# pmc2.net
KiCad netlist of a schematic drawn in EAGLE
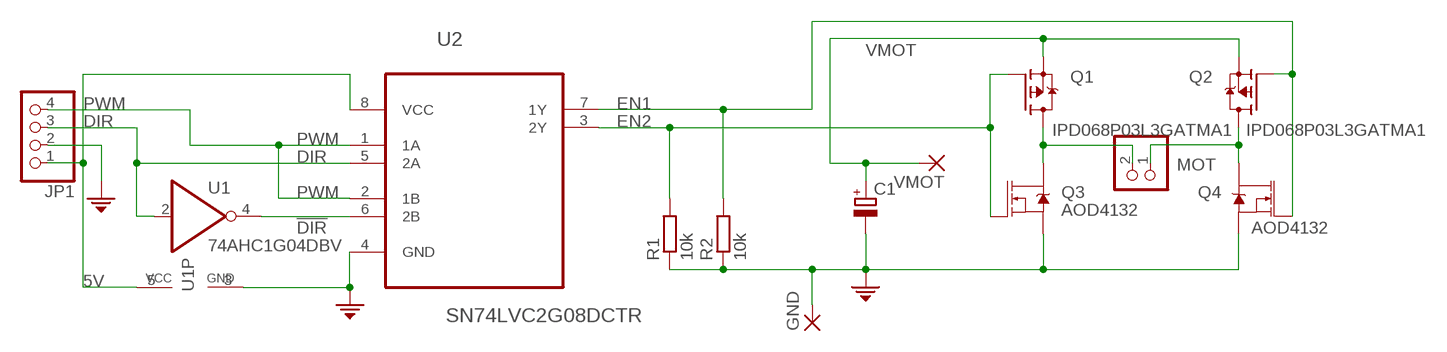
[diagram p0: schematic, sheet 1]

(export (version "E")
  (design (tool "Eeschema 10.0.6"))
  (components
    (comp (ref "C1")
      (value "CPOL-EUE5-13")
      (footprint "eagle-import:E5-13")
      (libsource (lib "eagle-import") (part "CPOL-EUE5-13"))
    )
    (comp (ref "GND")
      (value "SMD5")
      (footprint "eagle-import:SMD2,54-5,08")
      (libsource (lib "eagle-import") (part "SMD5"))
    )
    (comp (ref "JP1")
      (value "PINHD-1X4/90")
      (footprint "eagle-import:1X04_90")
      (libsource (lib "eagle-import") (part "PINHD-1X4/90"))
    )
    (comp (ref "MOT")
      (value "PINHD-1X2")
      (footprint "eagle-import:1X02")
      (libsource (lib "eagle-import") (part "PINHD-1X2"))
    )
    (comp (ref "Q1")
      (value "IPD068P03L3GATMA1")
      (footprint "eagle-import:TO252")
      (libsource (lib "eagle-import") (part "FDD4141TO252"))
    )
    (comp (ref "Q2")
      (value "IPD068P03L3GATMA1")
      (footprint "eagle-import:TO252")
      (libsource (lib "eagle-import") (part "FDD4141TO252"))
    )
    (comp (ref "Q3")
      (value "AOD4132")
      (footprint "eagle-import:DPAK")
      (libsource (lib "eagle-import") (part "MOSFET-NCH-FDD8780"))
    )
    (comp (ref "Q4")
      (value "AOD4132")
      (footprint "eagle-import:DPAK")
      (libsource (lib "eagle-import") (part "MOSFET-NCH-FDD8780"))
    )
    (comp (ref "R1")
      (value "10k")
      (footprint "eagle-import:R0603")
      (libsource (lib "eagle-import") (part "R-EU_R0603"))
    )
    (comp (ref "R2")
      (value "10k")
      (footprint "eagle-import:R0603")
      (libsource (lib "eagle-import") (part "R-EU_R0603"))
    )
    (comp (ref "U1")
      (value "74AHC1G04DBV")
      (footprint "eagle-import:SOT23-5")
      (libsource (lib "eagle-import") (part "741G04DBVAHC"))
    )
    (comp (ref "U2")
      (value "SN74LVC2G08DCTR")
      (footprint "eagle-import:SOP65P400X130-8N")
      (libsource (lib "eagle-import") (part "SN74LVC2G08DCTR"))
    )
    (comp (ref "VMOT")
      (value "SMD5")
      (footprint "eagle-import:SMD2,54-5,08")
      (libsource (lib "eagle-import") (part "SMD5"))
    )
  )
  (nets
    (net (code "1") (name "/5V") (class "Default")
      (node (ref "JP1") (pin "1") (pinfunction "1_1") (pintype "passive"))
      (node (ref "U1") (pin "5") (pinfunction "VCC_5") (pintype "power_in"))
      (node (ref "U2") (pin "8") (pinfunction "VCC_8") (pintype "power_in"))
    )
    (net (code "2") (name "/DIR") (class "Default")
      (node (ref "JP1") (pin "3") (pinfunction "3_3") (pintype "passive"))
      (node (ref "U1") (pin "2") (pinfunction "I_2") (pintype "input"))
      (node (ref "U2") (pin "5") (pinfunction "2A_5") (pintype "input"))
    )
    (net (code "3") (name "/EN1") (class "Default")
      (node (ref "Q2") (pin "1") (pinfunction "G_1") (pintype "passive"))
      (node (ref "Q4") (pin "1") (pinfunction "G_1") (pintype "bidirectional"))
      (node (ref "R2") (pin "2") (pinfunction "2_2") (pintype "passive"))
      (node (ref "U2") (pin "7") (pinfunction "1Y_7") (pintype "output"))
    )
    (net (code "4") (name "/EN2") (class "Default")
      (node (ref "Q1") (pin "1") (pinfunction "G_1") (pintype "passive"))
      (node (ref "Q3") (pin "1") (pinfunction "G_1") (pintype "bidirectional"))
      (node (ref "R1") (pin "2") (pinfunction "2_2") (pintype "passive"))
      (node (ref "U2") (pin "3") (pinfunction "2Y_3") (pintype "output"))
    )
    (net (code "5") (name "/PWM") (class "Default")
      (node (ref "JP1") (pin "4") (pinfunction "4_4") (pintype "passive"))
      (node (ref "U2") (pin "1") (pinfunction "1A_1") (pintype "input"))
      (node (ref "U2") (pin "2") (pinfunction "1B_2") (pintype "input"))
    )
    (net (code "6") (name "/VMOT") (class "Default")
      (node (ref "C1") (pin "+") (pinfunction "+_+") (pintype "passive"))
      (node (ref "Q1") (pin "2") (pinfunction "S_2") (pintype "passive"))
      (node (ref "Q2") (pin "2") (pinfunction "S_2") (pintype "passive"))
      (node (ref "VMOT") (pin "1") (pinfunction "P_1") (pintype "passive"))
    )
    (net (code "7") (name "/~{DIR}") (class "Default")
      (node (ref "U1") (pin "4") (pinfunction "O_4") (pintype "output"))
      (node (ref "U2") (pin "6") (pinfunction "2B_6") (pintype "input"))
    )
    (net (code "8") (name "GND") (class "Default")
      (node (ref "C1") (pin "-") (pinfunction "-_-") (pintype "passive"))
      (node (ref "GND") (pin "1") (pinfunction "P_1") (pintype "passive"))
      (node (ref "JP1") (pin "2") (pinfunction "2_2") (pintype "passive"))
      (node (ref "Q3") (pin "3") (pinfunction "S_3") (pintype "bidirectional"))
      (node (ref "Q4") (pin "3") (pinfunction "S_3") (pintype "bidirectional"))
      (node (ref "R1") (pin "1") (pinfunction "1_1") (pintype "passive"))
      (node (ref "R2") (pin "1") (pinfunction "1_1") (pintype "passive"))
      (node (ref "U1") (pin "3") (pinfunction "GND_3") (pintype "power_in"))
      (node (ref "U2") (pin "4") (pinfunction "GND_4") (pintype "passive"))
    )
    (net (code "9") (name "Net-(Q1-D)") (class "Default")
      (node (ref "MOT") (pin "2") (pinfunction "2_2") (pintype "passive"))
      (node (ref "Q1") (pin "3") (pinfunction "D_3") (pintype "passive"))
      (node (ref "Q3") (pin "4") (pinfunction "D_4") (pintype "bidirectional"))
    )
    (net (code "10") (name "Net-(Q2-D)") (class "Default")
      (node (ref "MOT") (pin "1") (pinfunction "1_1") (pintype "passive"))
      (node (ref "Q2") (pin "3") (pinfunction "D_3") (pintype "passive"))
      (node (ref "Q4") (pin "4") (pinfunction "D_4") (pintype "bidirectional"))
    )
  )
)
